# piezo-preamp-tickler_V2-RevA-01.net
KiCad netlist of a schematic drawn in EAGLE
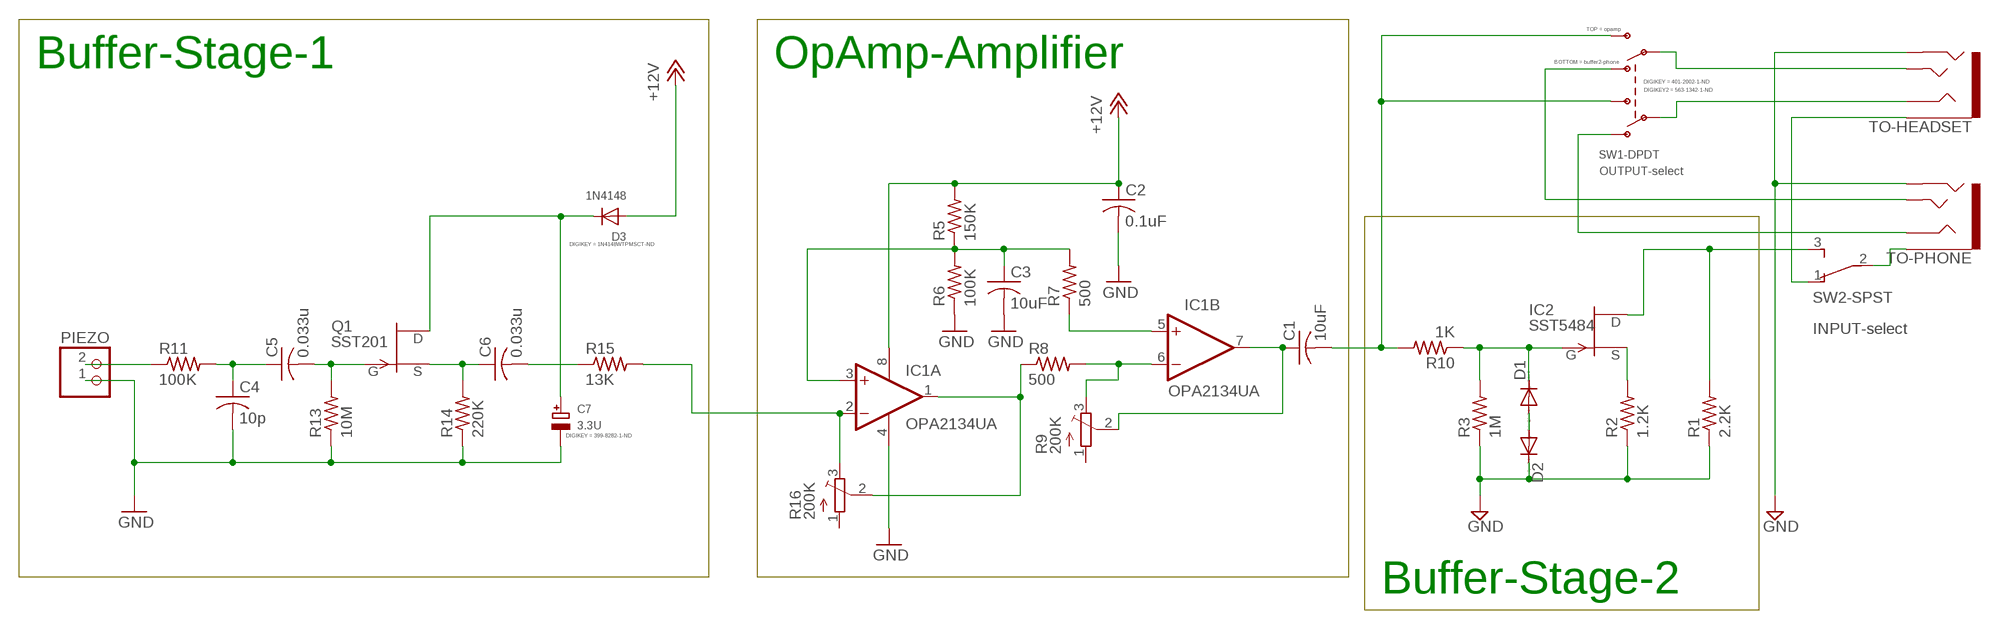
[diagram p0: schematic, sheet 1]
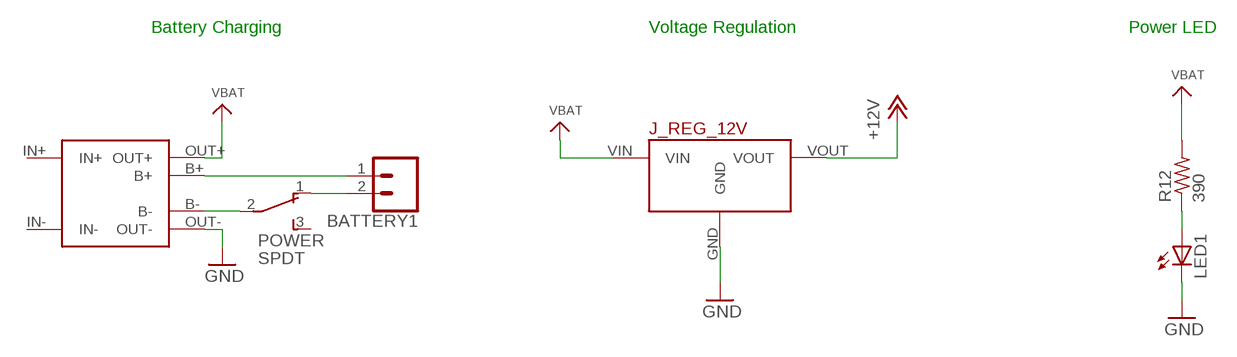
[diagram p1: schematic, sheet 2]

(export (version "E")
  (design (tool "Eeschema 10.0.6"))
  (components
    (comp (ref "BATTERY1")
      (value "CONN_02LOCK")
      (footprint "eagle-import:1X02_LOCK")
      (libsource (lib "eagle-import") (part "CONN_02LOCK"))
    )
    (comp (ref "J_REG_12V")
      (value "POLOLU_VOLTAGE_REGULATORS_3PIN")
      (footprint "eagle-import:POLOLU_5V-12V_STEPUP_U3V12F5-U3V12F12")
      (libsource (lib "eagle-import") (part "POLOLU_VOLTAGE_REGULATORS_3PIN"))
    )
    (comp (ref "LED1")
      (value "LED3MM")
      (footprint "eagle-import:LED3MM")
      (libsource (lib "eagle-import") (part "LED3MM"))
    )
    (comp (ref "POWER")
      (value "SPDT")
      (footprint "eagle-import:SWITCH_SPDT-TE-CONNECT")
      (libsource (lib "eagle-import") (part "SWITCH_SPDTTE-CONNECT"))
    )
    (comp (ref "R12")
      (value "390")
      (footprint "eagle-import:R0805")
      (libsource (lib "eagle-import") (part "R-US_R0805"))
    )
    (comp (ref "USB-LIPO-CHARGER")
      (value "TP4056-MODULE")
      (footprint "eagle-import:TP4056-LITHIUM-PROTECTED-MODULE")
      (libsource (lib "eagle-import") (part "TP4056-MODULE"))
    )
    (comp (ref "C1")
      (value "10uF")
      (footprint "eagle-import:C0805K")
      (libsource (lib "eagle-import") (part "C-USC0805K"))
    )
    (comp (ref "C2")
      (value "0.1uF")
      (footprint "eagle-import:C0805K")
      (libsource (lib "eagle-import") (part "C-USC0805K"))
    )
    (comp (ref "C3")
      (value "10uF")
      (footprint "eagle-import:C0805K")
      (libsource (lib "eagle-import") (part "C-USC0805K"))
    )
    (comp (ref "C4")
      (value "10p")
      (footprint "eagle-import:C0805K")
      (libsource (lib "eagle-import") (part "C-USC0805K"))
    )
    (comp (ref "C5")
      (value "0.033u")
      (footprint "eagle-import:C0805K")
      (libsource (lib "eagle-import") (part "C-USC0805K"))
    )
    (comp (ref "C6")
      (value "0.033u")
      (footprint "eagle-import:C0805K")
      (libsource (lib "eagle-import") (part "C-USC0805K"))
    )
    (comp (ref "C7")
      (value "3.3U")
      (footprint "eagle-import:EIA3216-18_A-R")
      (fields (field (name "DIGIKEY") "399-8282-1-ND"))
      (libsource (lib "eagle-import") (part "CAP_TANTALUMA/3216_REFLOW"))
    )
    (comp (ref "D1")
      (value "DIODE-SOD123")
      (footprint "eagle-import:SOD123")
      (libsource (lib "eagle-import") (part "DIODE-SOD123"))
    )
    (comp (ref "D2")
      (value "DIODE-SOD123")
      (footprint "eagle-import:SOD123")
      (libsource (lib "eagle-import") (part "DIODE-SOD123"))
    )
    (comp (ref "D3")
      (value "1N4148")
      (footprint "eagle-import:SOD-123")
      (fields (field (name "DIGIKEY") "1N4148WTPMSCT-ND"))
      (libsource (lib "eagle-import") (part "DIODESOD-123"))
    )
    (comp (ref "IC1")
      (value "OPA2134UA")
      (footprint "eagle-import:SO08")
      (libsource (lib "eagle-import") (part "OPA2UA134"))
    )
    (comp (ref "IC2")
      (value "SST5484")
      (footprint "eagle-import:SOT23")
      (libsource (lib "eagle-import") (part "?548SST4"))
    )
    (comp (ref "PIEZO")
      (value "JST_2PIN-THM")
      (footprint "eagle-import:JST-PH-2-THM")
      (libsource (lib "eagle-import") (part "JST_2PIN-THM"))
    )
    (comp (ref "Q1")
      (value "SST201")
      (footprint "eagle-import:SOT23")
      (libsource (lib "eagle-import") (part "?20SST1"))
    )
    (comp (ref "R1")
      (value "2.2K")
      (footprint "eagle-import:R0603")
      (libsource (lib "eagle-import") (part "R-US_R0603"))
    )
    (comp (ref "R2")
      (value "1.2K")
      (footprint "eagle-import:R0603")
      (libsource (lib "eagle-import") (part "R-US_R0603"))
    )
    (comp (ref "R3")
      (value "1M")
      (footprint "eagle-import:R0603")
      (libsource (lib "eagle-import") (part "R-US_R0603"))
    )
    (comp (ref "R5")
      (value "150K")
      (footprint "eagle-import:R0603")
      (libsource (lib "eagle-import") (part "R-US_R0603"))
    )
    (comp (ref "R6")
      (value "100K")
      (footprint "eagle-import:R0603")
      (libsource (lib "eagle-import") (part "R-US_R0603"))
    )
    (comp (ref "R7")
      (value "500")
      (footprint "eagle-import:R0603")
      (libsource (lib "eagle-import") (part "R-US_R0603"))
    )
    (comp (ref "R8")
      (value "500")
      (footprint "eagle-import:R0603")
      (libsource (lib "eagle-import") (part "R-US_R0603"))
    )
    (comp (ref "R9")
      (value "200K")
      (footprint "eagle-import:TC33X")
      (libsource (lib "eagle-import") (part "TRIMPOTTC33X"))
    )
    (comp (ref "R10")
      (value "1K")
      (footprint "eagle-import:R0603")
      (libsource (lib "eagle-import") (part "R-US_R0603"))
    )
    (comp (ref "R11")
      (value "100K")
      (footprint "eagle-import:R0603")
      (libsource (lib "eagle-import") (part "R-US_R0603"))
    )
    (comp (ref "R13")
      (value "10M")
      (footprint "eagle-import:R0603")
      (libsource (lib "eagle-import") (part "R-US_R0603"))
    )
    (comp (ref "R14")
      (value "220K")
      (footprint "eagle-import:R0603")
      (libsource (lib "eagle-import") (part "R-US_R0603"))
    )
    (comp (ref "R15")
      (value "13K")
      (footprint "eagle-import:R0603")
      (libsource (lib "eagle-import") (part "R-US_R0603"))
    )
    (comp (ref "R16")
      (value "200K")
      (footprint "eagle-import:TC33X")
      (libsource (lib "eagle-import") (part "TRIMPOTTC33X"))
    )
    (comp (ref "SW1-DPDT")
      (value "OUTPUT-select")
      (footprint "eagle-import:DPDT_SMT_JS202011SCQN")
      (fields
        (field (name "BOTTOM") "buffer2-phone")
        (field (name "DIGIKEY") "401-2002-1-ND")
        (field (name "DIGIKEY2") "563-1342-1-ND")
        (field (name "TOP") "opamp")
      )
      (libsource (lib "eagle-import") (part "SWITCH_DPDT"))
    )
    (comp (ref "SW2-SPST")
      (value "INPUT-select")
      (footprint "eagle-import:SWITCH_SPDT-TE-CONNECT")
      (libsource (lib "eagle-import") (part "SWITCH_SPDTTE-CONNECT"))
    )
    (comp (ref "TO-HEADSET")
      (value "AUDIO-JACK3LGPADS")
      (footprint "eagle-import:AUDIO-JACK-TRRS-SMD")
      (libsource (lib "eagle-import") (part "AUDIO-JACK3LGPADS"))
    )
    (comp (ref "TO-PHONE")
      (value "AUDIO-JACK3LGPADS")
      (footprint "eagle-import:AUDIO-JACK-TRRS-SMD")
      (libsource (lib "eagle-import") (part "AUDIO-JACK3LGPADS"))
    )
  )
  (nets
    (net (code "1") (name "+12V") (class "Default")
      (node (ref "C2") (pin "1") (pinfunction "1_1") (pintype "passive"))
      (node (ref "D3") (pin "A") (pinfunction "A_A") (pintype "passive"))
      (node (ref "IC1") (pin "8") (pinfunction "V+_8") (pintype "power_in"))
      (node (ref "J_REG_12V") (pin "VOUT") (pinfunction "VOUT_VOUT") (pintype "bidirectional"))
      (node (ref "R5") (pin "2") (pinfunction "2_2") (pintype "passive"))
    )
    (net (code "2") (name "GND") (class "Default")
      (node (ref "C2") (pin "2") (pinfunction "2_2") (pintype "passive"))
      (node (ref "C3") (pin "2") (pinfunction "2_2") (pintype "passive"))
      (node (ref "C4") (pin "2") (pinfunction "2_2") (pintype "passive"))
      (node (ref "C7") (pin "-") (pinfunction "-_-") (pintype "passive"))
      (node (ref "D2") (pin "C") (pinfunction "C_C") (pintype "passive"))
      (node (ref "IC1") (pin "4") (pinfunction "V-_4") (pintype "power_in"))
      (node (ref "J_REG_12V") (pin "GND") (pinfunction "GND_GND") (pintype "bidirectional"))
      (node (ref "LED1") (pin "K") (pinfunction "C_K") (pintype "passive"))
      (node (ref "PIEZO") (pin "1") (pinfunction "2_1") (pintype "passive"))
      (node (ref "R1") (pin "1") (pinfunction "1_1") (pintype "passive"))
      (node (ref "R13") (pin "1") (pinfunction "1_1") (pintype "passive"))
      (node (ref "R14") (pin "1") (pinfunction "1_1") (pintype "passive"))
      (node (ref "R2") (pin "1") (pinfunction "1_1") (pintype "passive"))
      (node (ref "R3") (pin "1") (pinfunction "1_1") (pintype "passive"))
      (node (ref "R6") (pin "1") (pinfunction "1_1") (pintype "passive"))
      (node (ref "TO-HEADSET") (pin "RING2") (pinfunction "RING2_RING2") (pintype "bidirectional"))
      (node (ref "TO-PHONE") (pin "RING2") (pinfunction "RING2_RING2") (pintype "bidirectional"))
      (node (ref "USB-LIPO-CHARGER") (pin "OUT-") (pinfunction "OUT-_OUT-") (pintype "power_in"))
    )
    (net (code "3") (name "IN+") (class "Default")
      (node (ref "USB-LIPO-CHARGER") (pin "IN+") (pinfunction "IN+_IN+") (pintype "power_in"))
    )
    (net (code "4") (name "IN-") (class "Default")
      (node (ref "USB-LIPO-CHARGER") (pin "IN-") (pinfunction "IN-_IN-") (pintype "power_in"))
    )
    (net (code "5") (name "Net-(BATTERY1-Pad1)") (class "Default")
      (node (ref "BATTERY1") (pin "1") (pinfunction "1_1") (pintype "passive"))
      (node (ref "USB-LIPO-CHARGER") (pin "B+") (pinfunction "B+_B+") (pintype "power_in"))
    )
    (net (code "6") (name "Net-(BATTERY1-Pad2)") (class "Default")
      (node (ref "BATTERY1") (pin "2") (pinfunction "2_2") (pintype "passive"))
      (node (ref "POWER") (pin "1") (pinfunction "1_1") (pintype "passive"))
    )
    (net (code "7") (name "Net-(C4-Pad1)") (class "Default")
      (node (ref "C4") (pin "1") (pinfunction "1_1") (pintype "passive"))
      (node (ref "C5") (pin "1") (pinfunction "1_1") (pintype "passive"))
      (node (ref "R11") (pin "2") (pinfunction "2_2") (pintype "passive"))
    )
    (net (code "8") (name "Net-(C6-Pad2)") (class "Default")
      (node (ref "C6") (pin "2") (pinfunction "2_2") (pintype "passive"))
      (node (ref "R15") (pin "1") (pinfunction "1_1") (pintype "passive"))
    )
    (net (code "9") (name "Net-(D1-PadA)") (class "Default")
      (node (ref "D1") (pin "A") (pinfunction "A_A") (pintype "passive"))
      (node (ref "D2") (pin "A") (pinfunction "A_A") (pintype "passive"))
    )
    (net (code "10") (name "Net-(IC1A-+IN)") (class "Default")
      (node (ref "C3") (pin "1") (pinfunction "1_1") (pintype "passive"))
      (node (ref "IC1") (pin "3") (pinfunction "+IN_3") (pintype "input"))
      (node (ref "R5") (pin "1") (pinfunction "1_1") (pintype "passive"))
      (node (ref "R6") (pin "2") (pinfunction "2_2") (pintype "passive"))
      (node (ref "R7") (pin "2") (pinfunction "2_2") (pintype "passive"))
    )
    (net (code "11") (name "Net-(IC1A--IN)") (class "Default")
      (node (ref "IC1") (pin "2") (pinfunction "-IN_2") (pintype "input"))
      (node (ref "R15") (pin "2") (pinfunction "2_2") (pintype "passive"))
      (node (ref "R16") (pin "3") (pinfunction "E_3") (pintype "passive"))
    )
    (net (code "12") (name "Net-(IC1A-OUT)") (class "Default")
      (node (ref "IC1") (pin "1") (pinfunction "OUT_1") (pintype "output"))
      (node (ref "R16") (pin "2") (pinfunction "S_2") (pintype "passive"))
      (node (ref "R8") (pin "1") (pinfunction "1_1") (pintype "passive"))
    )
    (net (code "13") (name "Net-(IC1B-+IN)") (class "Default")
      (node (ref "IC1") (pin "5") (pinfunction "+IN_5") (pintype "input"))
      (node (ref "R7") (pin "1") (pinfunction "1_1") (pintype "passive"))
    )
    (net (code "14") (name "Net-(IC1B--IN)") (class "Default")
      (node (ref "IC1") (pin "6") (pinfunction "-IN_6") (pintype "input"))
      (node (ref "R8") (pin "2") (pinfunction "2_2") (pintype "passive"))
      (node (ref "R9") (pin "3") (pinfunction "E_3") (pintype "passive"))
    )
    (net (code "15") (name "Net-(IC1B-OUT)") (class "Default")
      (node (ref "C1") (pin "1") (pinfunction "1_1") (pintype "passive"))
      (node (ref "IC1") (pin "7") (pinfunction "OUT_7") (pintype "output"))
      (node (ref "R9") (pin "2") (pinfunction "S_2") (pintype "passive"))
    )
    (net (code "16") (name "Net-(IC2-D)") (class "Default")
      (node (ref "IC2") (pin "1") (pinfunction "D_1") (pintype "passive"))
      (node (ref "R1") (pin "2") (pinfunction "2_2") (pintype "passive"))
      (node (ref "SW2-SPST") (pin "3") (pinfunction "3_3") (pintype "passive"))
    )
    (net (code "17") (name "Net-(IC2-G)") (class "Default")
      (node (ref "D1") (pin "C") (pinfunction "C_C") (pintype "passive"))
      (node (ref "IC2") (pin "3") (pinfunction "G_3") (pintype "passive"))
      (node (ref "R10") (pin "1") (pinfunction "1_1") (pintype "passive"))
      (node (ref "R3") (pin "2") (pinfunction "2_2") (pintype "passive"))
    )
    (net (code "18") (name "Net-(IC2-S)") (class "Default")
      (node (ref "IC2") (pin "2") (pinfunction "S_2") (pintype "passive"))
      (node (ref "R2") (pin "2") (pinfunction "2_2") (pintype "passive"))
    )
    (net (code "19") (name "Net-(LED1-PadA)") (class "Default")
      (node (ref "LED1") (pin "A") (pinfunction "A_A") (pintype "passive"))
      (node (ref "R12") (pin "1") (pinfunction "1_1") (pintype "passive"))
    )
    (net (code "20") (name "Net-(PIEZO-1)") (class "Default")
      (node (ref "PIEZO") (pin "2") (pinfunction "1_2") (pintype "passive"))
      (node (ref "R11") (pin "1") (pinfunction "1_1") (pintype "passive"))
    )
    (net (code "21") (name "Net-(POWER-Pad2)") (class "Default")
      (node (ref "POWER") (pin "2") (pinfunction "2_2") (pintype "passive"))
      (node (ref "USB-LIPO-CHARGER") (pin "B-") (pinfunction "B-_B-") (pintype "power_in"))
    )
    (net (code "22") (name "Net-(Q1-D)") (class "Default")
      (node (ref "C7") (pin "+") (pinfunction "+_+") (pintype "passive"))
      (node (ref "D3") (pin "C") (pinfunction "C_C") (pintype "passive"))
      (node (ref "Q1") (pin "1") (pinfunction "D_1") (pintype "passive"))
    )
    (net (code "23") (name "Net-(Q1-G)") (class "Default")
      (node (ref "C5") (pin "2") (pinfunction "2_2") (pintype "passive"))
      (node (ref "Q1") (pin "3") (pinfunction "G_3") (pintype "passive"))
      (node (ref "R13") (pin "2") (pinfunction "2_2") (pintype "passive"))
    )
    (net (code "24") (name "Net-(Q1-S)") (class "Default")
      (node (ref "C6") (pin "1") (pinfunction "1_1") (pintype "passive"))
      (node (ref "Q1") (pin "2") (pinfunction "S_2") (pintype "passive"))
      (node (ref "R14") (pin "2") (pinfunction "2_2") (pintype "passive"))
    )
    (net (code "25") (name "Net-(SW1-DPDT-O1)") (class "Default")
      (node (ref "SW1-DPDT") (pin "P$1") (pinfunction "O1_P$1") (pintype "passive"))
      (node (ref "TO-PHONE") (pin "RING1") (pinfunction "RING1_RING1") (pintype "bidirectional"))
    )
    (net (code "26") (name "Net-(SW1-DPDT-O2)") (class "Default")
      (node (ref "SW1-DPDT") (pin "P$6") (pinfunction "O2_P$6") (pintype "passive"))
      (node (ref "TO-PHONE") (pin "TIP") (pinfunction "TIP_TIP") (pintype "bidirectional"))
    )
    (net (code "27") (name "Net-(SW1-DPDT-P1)") (class "Default")
      (node (ref "SW1-DPDT") (pin "P$2") (pinfunction "P1_P$2") (pintype "passive"))
      (node (ref "TO-HEADSET") (pin "RING1") (pinfunction "RING1_RING1") (pintype "bidirectional"))
    )
    (net (code "28") (name "Net-(SW1-DPDT-P2)") (class "Default")
      (node (ref "SW1-DPDT") (pin "P$5") (pinfunction "P2_P$5") (pintype "passive"))
      (node (ref "TO-HEADSET") (pin "TIP") (pinfunction "TIP_TIP") (pintype "bidirectional"))
    )
    (net (code "29") (name "Net-(SW1-DPDT-S1)") (class "Default")
      (node (ref "C1") (pin "2") (pinfunction "2_2") (pintype "passive"))
      (node (ref "R10") (pin "2") (pinfunction "2_2") (pintype "passive"))
      (node (ref "SW1-DPDT") (pin "P$3") (pinfunction "S1_P$3") (pintype "passive"))
      (node (ref "SW1-DPDT") (pin "P$4") (pinfunction "S2_P$4") (pintype "passive"))
    )
    (net (code "30") (name "Net-(SW2-SPST-Pad1)") (class "Default")
      (node (ref "SW2-SPST") (pin "1") (pinfunction "1_1") (pintype "passive"))
      (node (ref "TO-HEADSET") (pin "EARTH") (pinfunction "EARTH_EARTH") (pintype "bidirectional"))
    )
    (net (code "31") (name "Net-(SW2-SPST-Pad2)") (class "Default")
      (node (ref "SW2-SPST") (pin "2") (pinfunction "2_2") (pintype "passive"))
      (node (ref "TO-PHONE") (pin "EARTH") (pinfunction "EARTH_EARTH") (pintype "bidirectional"))
    )
    (net (code "32") (name "VBAT") (class "Default")
      (node (ref "J_REG_12V") (pin "VIN") (pinfunction "VIN_VIN") (pintype "bidirectional"))
      (node (ref "R12") (pin "2") (pinfunction "2_2") (pintype "passive"))
      (node (ref "USB-LIPO-CHARGER") (pin "OUT+") (pinfunction "OUT+_OUT+") (pintype "power_in"))
    )
    (net (code "33") (name "unconnected-(POWER-Pad3)") (class "Default")
      (node (ref "POWER") (pin "3") (pinfunction "3_3") (pintype "passive"))
    )
    (net (code "34") (name "unconnected-(R9-A-Pad1)") (class "Default")
      (node (ref "R9") (pin "1") (pinfunction "A_1") (pintype "passive"))
    )
    (net (code "35") (name "unconnected-(R16-A-Pad1)") (class "Default")
      (node (ref "R16") (pin "1") (pinfunction "A_1") (pintype "passive"))
    )
  )
)
